# SPI_SD.net
KiCad netlist of a schematic drawn in Altium Designer
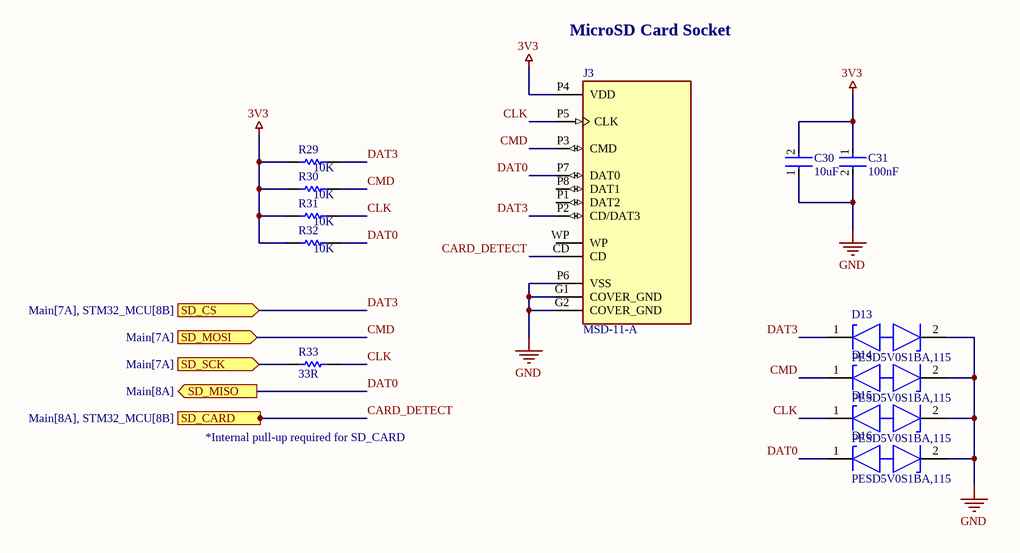
[diagram p0: SPI_SD.SchDoc]

(export (version "E")
  (design (tool "Eeschema 10.0.6"))
  (components
    (comp (ref "C30")
      (value "10uF")
      (footprint "FP-C1608-080-0_1-MFG")
      (description "Multilayer Ceramic Capacitors 10μF ±10% 10V X5R SMD 0603")
      (fields (field (name "VOLTAGE") "10V") (field (name "TOLERANCE") "10%"))
      (libsource (lib "Altium Content Vault") (part "236180d848d6139a670b325ea6854c9"))
    )
    (comp (ref "C31")
      (value "100nF")
      (footprint "FP-CGA3E-0_3-0_1-IPC_A")
      (description "Cap Ceramic 100nF 50V X7R 10% Pad SMD 0603 +125°C Automotive T/R")
      (fields (field (name "TOLERANCE") "10%") (field (name "VOLTAGE") "50V"))
      (libsource (lib "Altium Content Vault") (part "b4654b650e69147ec39a6b967a45e02"))
    )
    (comp (ref "D13")
      (value "PESD5V0S1BA,115")
      (footprint "FP-SOD323-CA-MFG")
      (description "TVS DIODE 5V 14V SOD323")
      (libsource (lib "Altium Content Vault") (part "f6dbb2535d6b2d347ec798cb4d032a4"))
    )
    (comp (ref "D14")
      (value "PESD5V0S1BA,115")
      (footprint "FP-SOD323-CA-MFG")
      (description "TVS DIODE 5V 14V SOD323")
      (libsource (lib "Altium Content Vault") (part "f6dbb2535d6b2d347ec798cb4d032a4"))
    )
    (comp (ref "D15")
      (value "PESD5V0S1BA,115")
      (footprint "FP-SOD323-CA-MFG")
      (description "TVS DIODE 5V 14V SOD323")
      (libsource (lib "Altium Content Vault") (part "f6dbb2535d6b2d347ec798cb4d032a4"))
    )
    (comp (ref "D16")
      (value "PESD5V0S1BA,115")
      (footprint "FP-SOD323-CA-MFG")
      (description "TVS DIODE 5V 14V SOD323")
      (libsource (lib "Altium Content Vault") (part "f6dbb2535d6b2d347ec798cb4d032a4"))
    )
    (comp (ref "J3")
      (value "MSD-11-A")
      (footprint "CUI_MSD-11-A")
      (fields (field (name "MF") "Same Sky"))
      (libsource (lib "MSD-11-A") (part "MSD-11-A"))
    )
    (comp (ref "R29")
      (value "10K")
      (footprint "RESC1609X55X30LL15T15")
      (description "Chip Resistor, 10 KOhm, +/- 1%, 0.1 W, -55 to 155 degC, 0603 (1608 Metric), RoHS, Tape and Reel")
      (fields (field (name "TOLERANCE") "1%") (field (name "MANUFACTURER") "Panasonic"))
      (libsource (lib "Altium Content Vault") (part "RES-2"))
    )
    (comp (ref "R30")
      (value "10K")
      (footprint "RESC1609X55X30LL15T15")
      (description "Chip Resistor, 10 KOhm, +/- 1%, 0.1 W, -55 to 155 degC, 0603 (1608 Metric), RoHS, Tape and Reel")
      (fields (field (name "TOLERANCE") "1%") (field (name "MANUFACTURER") "Panasonic"))
      (libsource (lib "Altium Content Vault") (part "RES-2"))
    )
    (comp (ref "R31")
      (value "10K")
      (footprint "RESC1609X55X30LL15T15")
      (description "Chip Resistor, 10 KOhm, +/- 1%, 0.1 W, -55 to 155 degC, 0603 (1608 Metric), RoHS, Tape and Reel")
      (fields (field (name "TOLERANCE") "1%") (field (name "MANUFACTURER") "Panasonic"))
      (libsource (lib "Altium Content Vault") (part "RES-2"))
    )
    (comp (ref "R32")
      (value "10K")
      (footprint "RESC1609X55X30LL15T15")
      (description "Chip Resistor, 10 KOhm, +/- 1%, 0.1 W, -55 to 155 degC, 0603 (1608 Metric), RoHS, Tape and Reel")
      (fields (field (name "TOLERANCE") "1%") (field (name "MANUFACTURER") "Panasonic"))
      (libsource (lib "Altium Content Vault") (part "RES-2"))
    )
    (comp (ref "R33")
      (value "33R")
      (footprint "RESC1608X55X25LL10T15")
      (description "Chip Resistor, 33 Ohm, +/- 1%, 0.1 W, -55 to 155 degC, 0603 (1608 Metric), RoHS, Tape and Reel")
      (fields (field (name "TOLERANCE") "1%") (field (name "MANUFACTURER") "Yageo"))
      (libsource (lib "Altium Content Vault") (part "RES-2"))
    )
  )
  (nets
    (net (code "1") (name "/CARD_DETECT") (class "Default")
      (node (ref "J3") (pin "CD") (pinfunction "CD_CD") (pintype "passive"))
    )
    (net (code "2") (name "/CLK") (class "Default")
      (node (ref "D15") (pin "1") (pinfunction "K1_1") (pintype "passive"))
      (node (ref "J3") (pin "P5") (pinfunction "CLK_P5") (pintype "input"))
      (node (ref "R31") (pin "2") (pinfunction "2_2") (pintype "passive"))
      (node (ref "R33") (pin "2") (pinfunction "2_2") (pintype "passive"))
    )
    (net (code "3") (name "/CMD") (class "Default")
      (node (ref "D14") (pin "1") (pinfunction "K1_1") (pintype "passive"))
      (node (ref "J3") (pin "P3") (pinfunction "CMD_P3") (pintype "bidirectional"))
      (node (ref "R30") (pin "2") (pinfunction "2_2") (pintype "passive"))
    )
    (net (code "4") (name "/DAT0") (class "Default")
      (node (ref "D16") (pin "1") (pinfunction "K1_1") (pintype "passive"))
      (node (ref "J3") (pin "P7") (pinfunction "DAT0_P7") (pintype "bidirectional"))
      (node (ref "R32") (pin "2") (pinfunction "2_2") (pintype "passive"))
    )
    (net (code "5") (name "/DAT3") (class "Default")
      (node (ref "D13") (pin "1") (pinfunction "K1_1") (pintype "passive"))
      (node (ref "J3") (pin "P2") (pinfunction "CD/DAT3_P2") (pintype "bidirectional"))
      (node (ref "R29") (pin "2") (pinfunction "2_2") (pintype "passive"))
    )
    (net (code "6") (name "/SD_SCK") (class "Default")
      (node (ref "R33") (pin "1") (pinfunction "1_1") (pintype "passive"))
    )
    (net (code "7") (name "3V3") (class "Default")
      (node (ref "C30") (pin "2") (pinfunction "2_2") (pintype "passive"))
      (node (ref "C31") (pin "1") (pinfunction "1_1") (pintype "passive"))
      (node (ref "J3") (pin "P4") (pinfunction "VDD_P4") (pintype "power_in"))
      (node (ref "R29") (pin "1") (pinfunction "1_1") (pintype "passive"))
      (node (ref "R30") (pin "1") (pinfunction "1_1") (pintype "passive"))
      (node (ref "R31") (pin "1") (pinfunction "1_1") (pintype "passive"))
      (node (ref "R32") (pin "1") (pinfunction "1_1") (pintype "passive"))
    )
    (net (code "8") (name "GND") (class "Default")
      (node (ref "C30") (pin "1") (pinfunction "1_1") (pintype "passive"))
      (node (ref "C31") (pin "2") (pinfunction "2_2") (pintype "passive"))
      (node (ref "D13") (pin "2") (pinfunction "K2_2") (pintype "passive"))
      (node (ref "D14") (pin "2") (pinfunction "K2_2") (pintype "passive"))
      (node (ref "D15") (pin "2") (pinfunction "K2_2") (pintype "passive"))
      (node (ref "D16") (pin "2") (pinfunction "K2_2") (pintype "passive"))
      (node (ref "J3") (pin "G1") (pinfunction "COVER_GND_G1") (pintype "power_in"))
      (node (ref "J3") (pin "G2") (pinfunction "COVER_GND_G2") (pintype "power_in"))
      (node (ref "J3") (pin "P6") (pinfunction "VSS_P6") (pintype "power_in"))
    )
    (net (code "9") (name "unconnected-(J3-DAT1-PadP8)") (class "Default")
      (node (ref "J3") (pin "P8") (pinfunction "DAT1_P8") (pintype "bidirectional"))
    )
    (net (code "10") (name "unconnected-(J3-DAT2-PadP1)") (class "Default")
      (node (ref "J3") (pin "P1") (pinfunction "DAT2_P1") (pintype "bidirectional"))
    )
    (net (code "11") (name "unconnected-(J3-PadWP)") (class "Default")
      (node (ref "J3") (pin "WP") (pinfunction "WP_WP") (pintype "passive"))
    )
  )
)
